# Arduino_Shield_Schematic.net
KiCad netlist of a schematic drawn in EAGLE
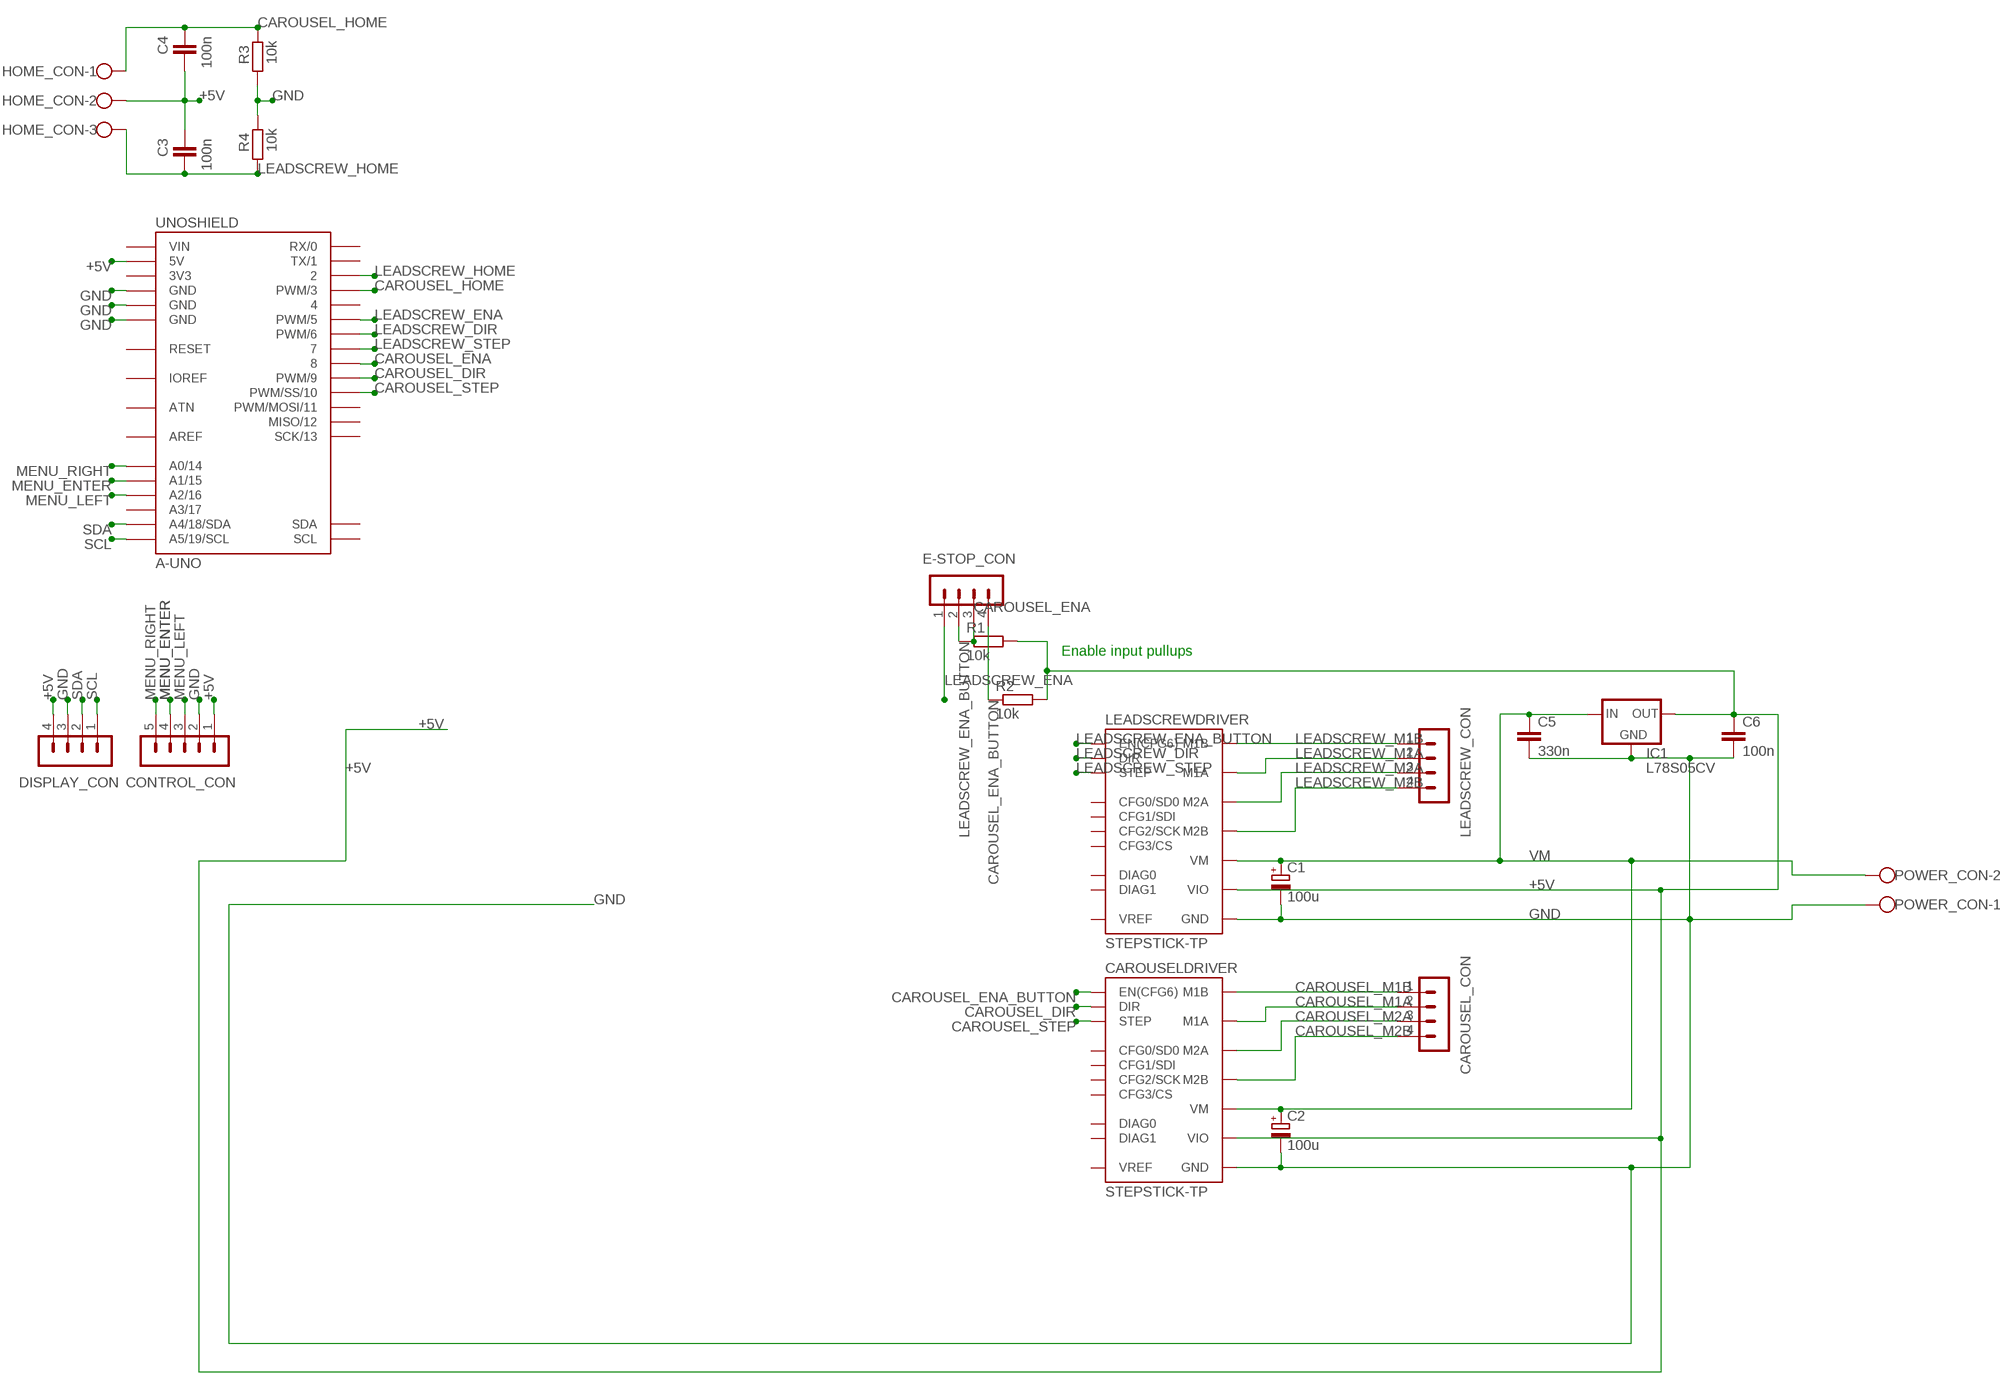
[diagram p0: schematic, sheet 1]

(export (version "E")
  (design (tool "Eeschema 10.0.6"))
  (components
    (comp (ref "C1")
      (value "100u")
      (footprint "eagle-import:E3,5-8")
      (libsource (lib "eagle-import") (part "CPOL-EUE3.5-8"))
    )
    (comp (ref "C2")
      (value "100u")
      (footprint "eagle-import:E3,5-8")
      (libsource (lib "eagle-import") (part "CPOL-EUE3.5-8"))
    )
    (comp (ref "C3")
      (value "100n")
      (footprint "eagle-import:C025-024X044")
      (libsource (lib "eagle-import") (part "C-EU025-024X044"))
    )
    (comp (ref "C4")
      (value "100n")
      (footprint "eagle-import:C025-024X044")
      (libsource (lib "eagle-import") (part "C-EU025-024X044"))
    )
    (comp (ref "C5")
      (value "330n")
      (footprint "eagle-import:C025-030X050")
      (libsource (lib "eagle-import") (part "C-EU025-030X050"))
    )
    (comp (ref "C6")
      (value "100n")
      (footprint "eagle-import:C025-030X050")
      (libsource (lib "eagle-import") (part "C-EU025-030X050"))
    )
    (comp (ref "CAROUSELDRIVER")
      (value "STEPSTICK-TP")
      (footprint "eagle-import:STEPSTICK_TP")
      (libsource (lib "eagle-import") (part "STEPSTICK-TP"))
    )
    (comp (ref "CAROUSEL_CON")
      (value "MA04-1")
      (footprint "eagle-import:MA04-1")
      (libsource (lib "eagle-import") (part "MA04-1"))
    )
    (comp (ref "CONTROL_CON")
      (value "MA05-1")
      (footprint "eagle-import:MA05-1")
      (libsource (lib "eagle-import") (part "MA05-1"))
    )
    (comp (ref "DISPLAY_CON")
      (value "MA04-1")
      (footprint "eagle-import:MA04-1")
      (libsource (lib "eagle-import") (part "MA04-1"))
    )
    (comp (ref "E-STOP_CON")
      (value "MA04-1")
      (footprint "eagle-import:MA04-1")
      (libsource (lib "eagle-import") (part "MA04-1"))
    )
    (comp (ref "HOME_CON")
      (value "W237-103")
      (footprint "eagle-import:W237-103")
      (fields (field (name "MPN") "237-103"))
      (libsource (lib "eagle-import") (part "W237-103"))
    )
    (comp (ref "IC1")
      (value "L78S05CV")
      (footprint "eagle-import:TO-220-STANDING")
      (fields (field (name "MF") "STMicroelectronics"))
      (libsource (lib "eagle-import") (part "L78S05CV"))
    )
    (comp (ref "LEADSCREWDRIVER")
      (value "STEPSTICK-TP")
      (footprint "eagle-import:STEPSTICK_TP")
      (libsource (lib "eagle-import") (part "STEPSTICK-TP"))
    )
    (comp (ref "LEADSCREW_CON")
      (value "MA04-1")
      (footprint "eagle-import:MA04-1")
      (libsource (lib "eagle-import") (part "MA04-1"))
    )
    (comp (ref "POWER_CON")
      (value "W237-102")
      (footprint "eagle-import:W237-102")
      (fields (field (name "MPN") "237-102"))
      (libsource (lib "eagle-import") (part "W237-102"))
    )
    (comp (ref "R1")
      (value "10k")
      (footprint "eagle-import:0207_12")
      (libsource (lib "eagle-import") (part "R-EU_0207/12"))
    )
    (comp (ref "R2")
      (value "10k")
      (footprint "eagle-import:0207_12")
      (libsource (lib "eagle-import") (part "R-EU_0207/12"))
    )
    (comp (ref "R3")
      (value "10k")
      (footprint "eagle-import:0207_10")
      (libsource (lib "eagle-import") (part "R-EU_0207/10"))
    )
    (comp (ref "R4")
      (value "10k")
      (footprint "eagle-import:0207_10")
      (libsource (lib "eagle-import") (part "R-EU_0207/10"))
    )
    (comp (ref "UNOSHIELD")
      (value "A-UNO")
      (footprint "eagle-import:A-UNO")
      (libsource (lib "eagle-import") (part "A-UNO"))
    )
  )
  (nets
    (net (code "1") (name "/+5V") (class "Default")
      (node (ref "C3") (pin "2") (pinfunction "2_2") (pintype "passive"))
      (node (ref "C4") (pin "1") (pinfunction "1_1") (pintype "passive"))
      (node (ref "C6") (pin "1") (pinfunction "1_1") (pintype "passive"))
      (node (ref "CAROUSELDRIVER") (pin "VIO") (pinfunction "VIO_VIO") (pintype "power_in"))
      (node (ref "CONTROL_CON") (pin "1") (pinfunction "1_1") (pintype "passive"))
      (node (ref "DISPLAY_CON") (pin "4") (pinfunction "4_4") (pintype "passive"))
      (node (ref "HOME_CON") (pin "2") (pinfunction "KL_2") (pintype "passive"))
      (node (ref "IC1") (pin "3") (pinfunction "OUT_3") (pintype "passive"))
      (node (ref "LEADSCREWDRIVER") (pin "VIO") (pinfunction "VIO_VIO") (pintype "power_in"))
      (node (ref "R1") (pin "2") (pinfunction "2_2") (pintype "passive"))
      (node (ref "R2") (pin "2") (pinfunction "2_2") (pintype "passive"))
      (node (ref "UNOSHIELD") (pin "5V") (pinfunction "5V_5V") (pintype "power_in"))
    )
    (net (code "2") (name "/3V3") (class "Default")
      (node (ref "UNOSHIELD") (pin "3V3") (pinfunction "3V3_3V3") (pintype "power_in"))
    )
    (net (code "3") (name "/AREF") (class "Default")
      (node (ref "UNOSHIELD") (pin "AREF") (pinfunction "AREF_AREF") (pintype "power_in"))
    )
    (net (code "4") (name "/CAROUSEL_DIR") (class "Default")
      (node (ref "CAROUSELDRIVER") (pin "DIR") (pinfunction "DIR_DIR") (pintype "bidirectional"))
      (node (ref "UNOSHIELD") (pin "9") (pinfunction "PWM/9_9") (pintype "bidirectional"))
    )
    (net (code "5") (name "/CAROUSEL_ENA") (class "Default")
      (node (ref "E-STOP_CON") (pin "3") (pinfunction "3_3") (pintype "passive"))
      (node (ref "UNOSHIELD") (pin "8") (pinfunction "8_8") (pintype "bidirectional"))
    )
    (net (code "6") (name "/CAROUSEL_ENA_BUTTON") (class "Default")
      (node (ref "CAROUSELDRIVER") (pin "EN") (pinfunction "EN(CFG6)_EN") (pintype "bidirectional"))
      (node (ref "E-STOP_CON") (pin "4") (pinfunction "4_4") (pintype "passive"))
      (node (ref "R2") (pin "1") (pinfunction "1_1") (pintype "passive"))
    )
    (net (code "7") (name "/CAROUSEL_HOME") (class "Default")
      (node (ref "C4") (pin "2") (pinfunction "2_2") (pintype "passive"))
      (node (ref "HOME_CON") (pin "1") (pinfunction "KL_1") (pintype "passive"))
      (node (ref "R3") (pin "2") (pinfunction "2_2") (pintype "passive"))
      (node (ref "UNOSHIELD") (pin "3") (pinfunction "PWM/3_3") (pintype "bidirectional"))
    )
    (net (code "8") (name "/CAROUSEL_M1A") (class "Default")
      (node (ref "CAROUSELDRIVER") (pin "M1A") (pinfunction "M1A_M1A") (pintype "output"))
      (node (ref "CAROUSEL_CON") (pin "2") (pinfunction "2_2") (pintype "passive"))
    )
    (net (code "9") (name "/CAROUSEL_M1B") (class "Default")
      (node (ref "CAROUSELDRIVER") (pin "M1B") (pinfunction "M1B_M1B") (pintype "output"))
      (node (ref "CAROUSEL_CON") (pin "1") (pinfunction "1_1") (pintype "passive"))
    )
    (net (code "10") (name "/CAROUSEL_M2A") (class "Default")
      (node (ref "CAROUSELDRIVER") (pin "M2A") (pinfunction "M2A_M2A") (pintype "output"))
      (node (ref "CAROUSEL_CON") (pin "3") (pinfunction "3_3") (pintype "passive"))
    )
    (net (code "11") (name "/CAROUSEL_M2B") (class "Default")
      (node (ref "CAROUSELDRIVER") (pin "M2B") (pinfunction "M2B_M2B") (pintype "output"))
      (node (ref "CAROUSEL_CON") (pin "4") (pinfunction "4_4") (pintype "passive"))
    )
    (net (code "12") (name "/CAROUSEL_STEP") (class "Default")
      (node (ref "CAROUSELDRIVER") (pin "STEP") (pinfunction "STEP_STEP") (pintype "bidirectional"))
      (node (ref "UNOSHIELD") (pin "10") (pinfunction "PWM/SS/10_10") (pintype "bidirectional"))
    )
    (net (code "13") (name "/GND") (class "Default")
      (node (ref "C1") (pin "-") (pinfunction "-_-") (pintype "passive"))
      (node (ref "C2") (pin "-") (pinfunction "-_-") (pintype "passive"))
      (node (ref "C5") (pin "2") (pinfunction "2_2") (pintype "passive"))
      (node (ref "C6") (pin "2") (pinfunction "2_2") (pintype "passive"))
      (node (ref "CAROUSELDRIVER") (pin "GND@1") (pinfunction "GND_GND@1") (pintype "power_in"))
      (node (ref "CAROUSELDRIVER") (pin "GND@2") (pinfunction "GND_GND@2") (pintype "power_in"))
      (node (ref "CONTROL_CON") (pin "2") (pinfunction "2_2") (pintype "passive"))
      (node (ref "DISPLAY_CON") (pin "3") (pinfunction "3_3") (pintype "passive"))
      (node (ref "IC1") (pin "2") (pinfunction "GND_2") (pintype "input"))
      (node (ref "LEADSCREWDRIVER") (pin "GND@1") (pinfunction "GND_GND@1") (pintype "power_in"))
      (node (ref "LEADSCREWDRIVER") (pin "GND@2") (pinfunction "GND_GND@2") (pintype "power_in"))
      (node (ref "POWER_CON") (pin "1") (pinfunction "KL_1") (pintype "passive"))
      (node (ref "R3") (pin "1") (pinfunction "1_1") (pintype "passive"))
      (node (ref "R4") (pin "2") (pinfunction "2_2") (pintype "passive"))
      (node (ref "UNOSHIELD") (pin "GND@1") (pinfunction "GND_GND@1") (pintype "power_in"))
      (node (ref "UNOSHIELD") (pin "GND@2") (pinfunction "GND_GND@2") (pintype "power_in"))
      (node (ref "UNOSHIELD") (pin "GND@3") (pinfunction "GND_GND@3") (pintype "power_in"))
    )
    (net (code "14") (name "/IOREF") (class "Default")
      (node (ref "UNOSHIELD") (pin "IOREF") (pinfunction "IOREF_IOREF") (pintype "power_in"))
    )
    (net (code "15") (name "/LEADSCREW_DIR") (class "Default")
      (node (ref "LEADSCREWDRIVER") (pin "DIR") (pinfunction "DIR_DIR") (pintype "bidirectional"))
      (node (ref "UNOSHIELD") (pin "6") (pinfunction "PWM/6_6") (pintype "bidirectional"))
    )
    (net (code "16") (name "/LEADSCREW_ENA") (class "Default")
      (node (ref "E-STOP_CON") (pin "1") (pinfunction "1_1") (pintype "passive"))
      (node (ref "UNOSHIELD") (pin "5") (pinfunction "PWM/5_5") (pintype "bidirectional"))
    )
    (net (code "17") (name "/LEADSCREW_ENA_BUTTON") (class "Default")
      (node (ref "E-STOP_CON") (pin "2") (pinfunction "2_2") (pintype "passive"))
      (node (ref "LEADSCREWDRIVER") (pin "EN") (pinfunction "EN(CFG6)_EN") (pintype "bidirectional"))
      (node (ref "R1") (pin "1") (pinfunction "1_1") (pintype "passive"))
    )
    (net (code "18") (name "/LEADSCREW_HOME") (class "Default")
      (node (ref "C3") (pin "1") (pinfunction "1_1") (pintype "passive"))
      (node (ref "HOME_CON") (pin "3") (pinfunction "KL_3") (pintype "passive"))
      (node (ref "R4") (pin "1") (pinfunction "1_1") (pintype "passive"))
      (node (ref "UNOSHIELD") (pin "2") (pinfunction "2_2") (pintype "bidirectional"))
    )
    (net (code "19") (name "/LEADSCREW_M1A") (class "Default")
      (node (ref "LEADSCREWDRIVER") (pin "M1A") (pinfunction "M1A_M1A") (pintype "output"))
      (node (ref "LEADSCREW_CON") (pin "2") (pinfunction "2_2") (pintype "passive"))
    )
    (net (code "20") (name "/LEADSCREW_M1B") (class "Default")
      (node (ref "LEADSCREWDRIVER") (pin "M1B") (pinfunction "M1B_M1B") (pintype "output"))
      (node (ref "LEADSCREW_CON") (pin "1") (pinfunction "1_1") (pintype "passive"))
    )
    (net (code "21") (name "/LEADSCREW_M2A") (class "Default")
      (node (ref "LEADSCREWDRIVER") (pin "M2A") (pinfunction "M2A_M2A") (pintype "output"))
      (node (ref "LEADSCREW_CON") (pin "3") (pinfunction "3_3") (pintype "passive"))
    )
    (net (code "22") (name "/LEADSCREW_M2B") (class "Default")
      (node (ref "LEADSCREWDRIVER") (pin "M2B") (pinfunction "M2B_M2B") (pintype "output"))
      (node (ref "LEADSCREW_CON") (pin "4") (pinfunction "4_4") (pintype "passive"))
    )
    (net (code "23") (name "/LEADSCREW_STEP") (class "Default")
      (node (ref "LEADSCREWDRIVER") (pin "STEP") (pinfunction "STEP_STEP") (pintype "bidirectional"))
      (node (ref "UNOSHIELD") (pin "7") (pinfunction "7_7") (pintype "bidirectional"))
    )
    (net (code "24") (name "/MENU_ENTER") (class "Default")
      (node (ref "CONTROL_CON") (pin "4") (pinfunction "4_4") (pintype "passive"))
      (node (ref "UNOSHIELD") (pin "A1") (pinfunction "A1/15_A1") (pintype "bidirectional"))
    )
    (net (code "25") (name "/MENU_LEFT") (class "Default")
      (node (ref "CONTROL_CON") (pin "3") (pinfunction "3_3") (pintype "passive"))
      (node (ref "UNOSHIELD") (pin "A2") (pinfunction "A2/16_A2") (pintype "bidirectional"))
    )
    (net (code "26") (name "/MENU_RIGHT") (class "Default")
      (node (ref "CONTROL_CON") (pin "5") (pinfunction "5_5") (pintype "passive"))
      (node (ref "UNOSHIELD") (pin "A0") (pinfunction "A0/14_A0") (pintype "bidirectional"))
    )
    (net (code "27") (name "/SCL") (class "Default")
      (node (ref "DISPLAY_CON") (pin "1") (pinfunction "1_1") (pintype "passive"))
      (node (ref "UNOSHIELD") (pin "A5") (pinfunction "A5/19/SCL_A5") (pintype "bidirectional"))
    )
    (net (code "28") (name "/SDA") (class "Default")
      (node (ref "DISPLAY_CON") (pin "2") (pinfunction "2_2") (pintype "passive"))
      (node (ref "UNOSHIELD") (pin "A4") (pinfunction "A4/18/SDA_A4") (pintype "bidirectional"))
    )
    (net (code "29") (name "/VIN") (class "Default")
      (node (ref "UNOSHIELD") (pin "VIN") (pinfunction "VIN_VIN") (pintype "power_in"))
    )
    (net (code "30") (name "/VM") (class "Default")
      (node (ref "C1") (pin "+") (pinfunction "+_+") (pintype "passive"))
      (node (ref "C2") (pin "+") (pinfunction "+_+") (pintype "passive"))
      (node (ref "C5") (pin "1") (pinfunction "1_1") (pintype "passive"))
      (node (ref "CAROUSELDRIVER") (pin "VM") (pinfunction "VM_VM") (pintype "power_in"))
      (node (ref "IC1") (pin "1") (pinfunction "IN_1") (pintype "input"))
      (node (ref "LEADSCREWDRIVER") (pin "VM") (pinfunction "VM_VM") (pintype "power_in"))
      (node (ref "POWER_CON") (pin "2") (pinfunction "KL_2") (pintype "passive"))
    )
    (net (code "31") (name "unconnected-(CAROUSELDRIVER-CFG0{slash}SD0-PadNC{slash}CFG0)") (class "Default")
      (node (ref "CAROUSELDRIVER") (pin "NC/CFG0") (pinfunction "CFG0/SD0_NC/CFG0") (pintype "bidirectional"))
    )
    (net (code "32") (name "unconnected-(CAROUSELDRIVER-CFG1{slash}SDI-PadCFG1)") (class "Default")
      (node (ref "CAROUSELDRIVER") (pin "CFG1") (pinfunction "CFG1/SDI_CFG1") (pintype "bidirectional"))
    )
    (net (code "33") (name "unconnected-(CAROUSELDRIVER-CFG2{slash}SCK-PadCFG2)") (class "Default")
      (node (ref "CAROUSELDRIVER") (pin "CFG2") (pinfunction "CFG2/SCK_CFG2") (pintype "bidirectional"))
    )
    (net (code "34") (name "unconnected-(CAROUSELDRIVER-CFG3{slash}CS-PadCFG3)") (class "Default")
      (node (ref "CAROUSELDRIVER") (pin "CFG3") (pinfunction "CFG3/CS_CFG3") (pintype "bidirectional"))
    )
    (net (code "35") (name "unconnected-(CAROUSELDRIVER-PadDIAG0)") (class "Default")
      (node (ref "CAROUSELDRIVER") (pin "DIAG0") (pinfunction "DIAG0_DIAG0") (pintype "bidirectional"))
    )
    (net (code "36") (name "unconnected-(CAROUSELDRIVER-PadDIAG1)") (class "Default")
      (node (ref "CAROUSELDRIVER") (pin "DIAG1") (pinfunction "DIAG1_DIAG1") (pintype "bidirectional"))
    )
    (net (code "37") (name "unconnected-(CAROUSELDRIVER-PadVREF)") (class "Default")
      (node (ref "CAROUSELDRIVER") (pin "VREF") (pinfunction "VREF_VREF") (pintype "passive"))
    )
    (net (code "38") (name "unconnected-(LEADSCREWDRIVER-CFG0{slash}SD0-PadNC{slash}CFG0)") (class "Default")
      (node (ref "LEADSCREWDRIVER") (pin "NC/CFG0") (pinfunction "CFG0/SD0_NC/CFG0") (pintype "bidirectional"))
    )
    (net (code "39") (name "unconnected-(LEADSCREWDRIVER-CFG1{slash}SDI-PadCFG1)") (class "Default")
      (node (ref "LEADSCREWDRIVER") (pin "CFG1") (pinfunction "CFG1/SDI_CFG1") (pintype "bidirectional"))
    )
    (net (code "40") (name "unconnected-(LEADSCREWDRIVER-CFG2{slash}SCK-PadCFG2)") (class "Default")
      (node (ref "LEADSCREWDRIVER") (pin "CFG2") (pinfunction "CFG2/SCK_CFG2") (pintype "bidirectional"))
    )
    (net (code "41") (name "unconnected-(LEADSCREWDRIVER-CFG3{slash}CS-PadCFG3)") (class "Default")
      (node (ref "LEADSCREWDRIVER") (pin "CFG3") (pinfunction "CFG3/CS_CFG3") (pintype "bidirectional"))
    )
    (net (code "42") (name "unconnected-(LEADSCREWDRIVER-PadDIAG0)") (class "Default")
      (node (ref "LEADSCREWDRIVER") (pin "DIAG0") (pinfunction "DIAG0_DIAG0") (pintype "bidirectional"))
    )
    (net (code "43") (name "unconnected-(LEADSCREWDRIVER-PadDIAG1)") (class "Default")
      (node (ref "LEADSCREWDRIVER") (pin "DIAG1") (pinfunction "DIAG1_DIAG1") (pintype "bidirectional"))
    )
    (net (code "44") (name "unconnected-(LEADSCREWDRIVER-PadVREF)") (class "Default")
      (node (ref "LEADSCREWDRIVER") (pin "VREF") (pinfunction "VREF_VREF") (pintype "passive"))
    )
    (net (code "45") (name "unconnected-(UNOSHIELD-A3{slash}17-PadA3)") (class "Default")
      (node (ref "UNOSHIELD") (pin "A3") (pinfunction "A3/17_A3") (pintype "bidirectional"))
    )
    (net (code "46") (name "unconnected-(UNOSHIELD-MISO{slash}12-Pad12)") (class "Default")
      (node (ref "UNOSHIELD") (pin "12") (pinfunction "MISO/12_12") (pintype "bidirectional"))
    )
    (net (code "47") (name "unconnected-(UNOSHIELD-PWM{slash}MOSI{slash}11-Pad11)") (class "Default")
      (node (ref "UNOSHIELD") (pin "11") (pinfunction "PWM/MOSI/11_11") (pintype "bidirectional"))
    )
    (net (code "48") (name "unconnected-(UNOSHIELD-Pad4)") (class "Default")
      (node (ref "UNOSHIELD") (pin "4") (pinfunction "4_4") (pintype "bidirectional"))
    )
    (net (code "49") (name "unconnected-(UNOSHIELD-PadATN)") (class "Default")
      (node (ref "UNOSHIELD") (pin "ATN") (pinfunction "ATN_ATN") (pintype "bidirectional"))
    )
    (net (code "50") (name "unconnected-(UNOSHIELD-PadSCL)") (class "Default")
      (node (ref "UNOSHIELD") (pin "SCL") (pinfunction "SCL_SCL") (pintype "bidirectional"))
    )
    (net (code "51") (name "unconnected-(UNOSHIELD-PadSDA)") (class "Default")
      (node (ref "UNOSHIELD") (pin "SDA") (pinfunction "SDA_SDA") (pintype "bidirectional"))
    )
    (net (code "52") (name "unconnected-(UNOSHIELD-RESET-PadRST)") (class "Default")
      (node (ref "UNOSHIELD") (pin "RST") (pinfunction "RESET_RST") (pintype "bidirectional"))
    )
    (net (code "53") (name "unconnected-(UNOSHIELD-RX{slash}0-Pad0)") (class "Default")
      (node (ref "UNOSHIELD") (pin "0") (pinfunction "RX/0_0") (pintype "bidirectional"))
    )
    (net (code "54") (name "unconnected-(UNOSHIELD-SCK{slash}13-Pad13)") (class "Default")
      (node (ref "UNOSHIELD") (pin "13") (pinfunction "SCK/13_13") (pintype "bidirectional"))
    )
    (net (code "55") (name "unconnected-(UNOSHIELD-TX{slash}1-Pad1)") (class "Default")
      (node (ref "UNOSHIELD") (pin "1") (pinfunction "TX/1_1") (pintype "bidirectional"))
    )
  )
)
